# 4__Connectors___IO.net
KiCad netlist of a schematic drawn in Altium Designer
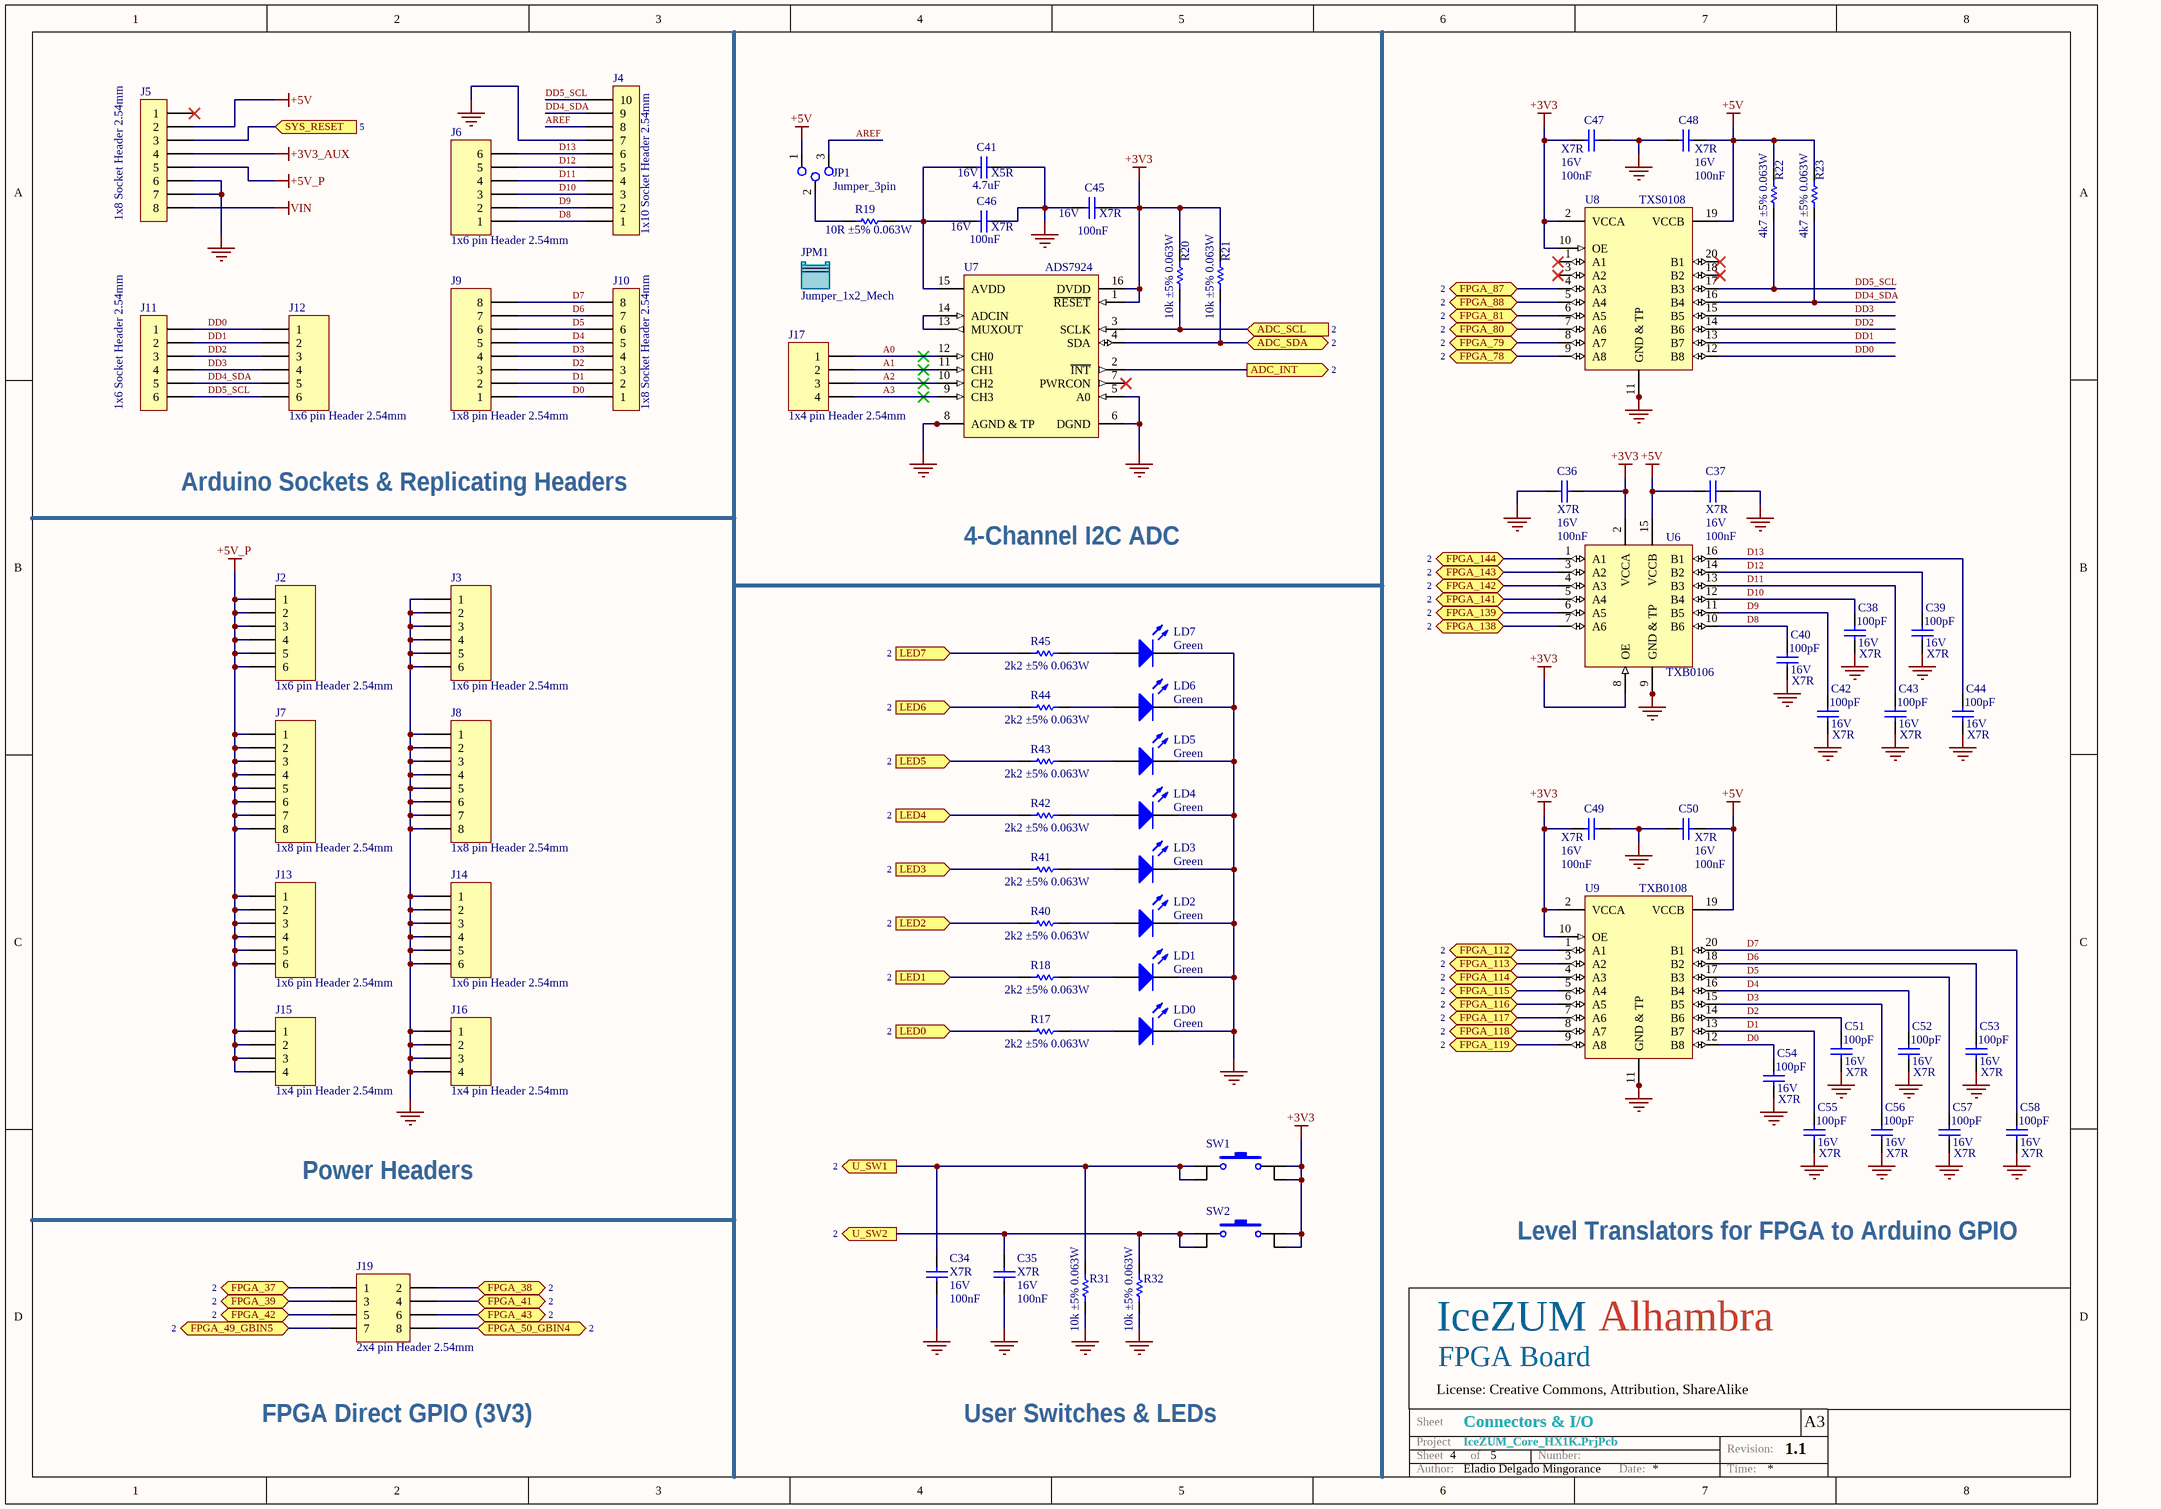
[diagram p0: [4]_Connectors_&_IO.SchDoc]

(export (version "E")
  (design (tool "Eeschema 10.0.6"))
  (components
    (comp (ref "C34")
      (value "Capacitor")
      (footprint "C0402")
      (description "Capacitor SMD")
      (fields
        (field (name "DIELECTRIC") "X7R")
        (field (name "VOLTAGE") "16V")
        (field (name "CAPACITANCE") "100nF")
        (field (name "PART NUMBER") "C0402_100nF_16V_±10%")
        (field (name "TOLERANCE") "±10%")
      )
      (libsource (lib "Pasives_Capacitor_SMD") (part "Capacitor"))
    )
    (comp (ref "C35")
      (value "Capacitor")
      (footprint "C0402")
      (description "Capacitor SMD")
      (fields
        (field (name "DIELECTRIC") "X7R")
        (field (name "VOLTAGE") "16V")
        (field (name "CAPACITANCE") "100nF")
        (field (name "PART NUMBER") "C0402_100nF_16V_±10%")
        (field (name "TOLERANCE") "±10%")
      )
      (libsource (lib "Pasives_Capacitor_SMD") (part "Capacitor"))
    )
    (comp (ref "C36")
      (value "Capacitor")
      (footprint "C0402")
      (description "Capacitor SMD")
      (fields
        (field (name "DIELECTRIC") "X7R")
        (field (name "VOLTAGE") "16V")
        (field (name "CAPACITANCE") "100nF")
        (field (name "PART NUMBER") "C0402_100nF_16V_±10%")
        (field (name "TOLERANCE") "±10%")
      )
      (libsource (lib "Pasives_Capacitor_SMD") (part "Capacitor"))
    )
    (comp (ref "C37")
      (value "Capacitor")
      (footprint "C0402")
      (description "Capacitor SMD")
      (fields
        (field (name "DIELECTRIC") "X7R")
        (field (name "VOLTAGE") "16V")
        (field (name "CAPACITANCE") "100nF")
        (field (name "PART NUMBER") "C0402_100nF_16V_±10%")
        (field (name "TOLERANCE") "±10%")
      )
      (libsource (lib "Pasives_Capacitor_SMD") (part "Capacitor"))
    )
    (comp (ref "C38")
      (value "Capacitor")
      (footprint "C0402")
      (description "Capacitor SMD")
      (fields
        (field (name "DIELECTRIC") "X7R")
        (field (name "VOLTAGE") "16V")
        (field (name "CAPACITANCE") "100pF")
        (field (name "PART NUMBER") "C0402_100pF_16V_±10%")
        (field (name "TOLERANCE") "±10%")
      )
      (libsource (lib "Pasives_Capacitor_SMD") (part "Capacitor"))
    )
    (comp (ref "C39")
      (value "Capacitor")
      (footprint "C0402")
      (description "Capacitor SMD")
      (fields
        (field (name "DIELECTRIC") "X7R")
        (field (name "VOLTAGE") "16V")
        (field (name "CAPACITANCE") "100pF")
        (field (name "PART NUMBER") "C0402_100pF_16V_±10%")
        (field (name "TOLERANCE") "±10%")
      )
      (libsource (lib "Pasives_Capacitor_SMD") (part "Capacitor"))
    )
    (comp (ref "C40")
      (value "Capacitor")
      (footprint "C0402")
      (description "Capacitor SMD")
      (fields
        (field (name "DIELECTRIC") "X7R")
        (field (name "VOLTAGE") "16V")
        (field (name "CAPACITANCE") "100pF")
        (field (name "PART NUMBER") "C0402_100pF_16V_±10%")
        (field (name "TOLERANCE") "±10%")
      )
      (libsource (lib "Pasives_Capacitor_SMD") (part "Capacitor"))
    )
    (comp (ref "C41")
      (value "Capacitor")
      (footprint "C0603")
      (description "Capacitor SMD")
      (fields
        (field (name "DIELECTRIC") "X5R")
        (field (name "VOLTAGE") "16V")
        (field (name "CAPACITANCE") "4.7uF")
        (field (name "PART NUMBER") "C0603_4.7uF_16V_±10%")
        (field (name "TOLERANCE") "±10%")
      )
      (libsource (lib "Pasives_Capacitor_SMD") (part "Capacitor"))
    )
    (comp (ref "C42")
      (value "Capacitor")
      (footprint "C0402")
      (description "Capacitor SMD")
      (fields
        (field (name "DIELECTRIC") "X7R")
        (field (name "VOLTAGE") "16V")
        (field (name "CAPACITANCE") "100pF")
        (field (name "PART NUMBER") "C0402_100pF_16V_±10%")
        (field (name "TOLERANCE") "±10%")
      )
      (libsource (lib "Pasives_Capacitor_SMD") (part "Capacitor"))
    )
    (comp (ref "C43")
      (value "Capacitor")
      (footprint "C0402")
      (description "Capacitor SMD")
      (fields
        (field (name "DIELECTRIC") "X7R")
        (field (name "VOLTAGE") "16V")
        (field (name "CAPACITANCE") "100pF")
        (field (name "PART NUMBER") "C0402_100pF_16V_±10%")
        (field (name "TOLERANCE") "±10%")
      )
      (libsource (lib "Pasives_Capacitor_SMD") (part "Capacitor"))
    )
    (comp (ref "C44")
      (value "Capacitor")
      (footprint "C0402")
      (description "Capacitor SMD")
      (fields
        (field (name "DIELECTRIC") "X7R")
        (field (name "VOLTAGE") "16V")
        (field (name "CAPACITANCE") "100pF")
        (field (name "PART NUMBER") "C0402_100pF_16V_±10%")
        (field (name "TOLERANCE") "±10%")
      )
      (libsource (lib "Pasives_Capacitor_SMD") (part "Capacitor"))
    )
    (comp (ref "C45")
      (value "Capacitor")
      (footprint "C0402")
      (description "Capacitor SMD")
      (fields
        (field (name "DIELECTRIC") "X7R")
        (field (name "VOLTAGE") "16V")
        (field (name "CAPACITANCE") "100nF")
        (field (name "PART NUMBER") "C0402_100nF_16V_±10%")
        (field (name "TOLERANCE") "±10%")
      )
      (libsource (lib "Pasives_Capacitor_SMD") (part "Capacitor"))
    )
    (comp (ref "C46")
      (value "Capacitor")
      (footprint "C0402")
      (description "Capacitor SMD")
      (fields
        (field (name "DIELECTRIC") "X7R")
        (field (name "VOLTAGE") "16V")
        (field (name "CAPACITANCE") "100nF")
        (field (name "PART NUMBER") "C0402_100nF_16V_±10%")
        (field (name "TOLERANCE") "±10%")
      )
      (libsource (lib "Pasives_Capacitor_SMD") (part "Capacitor"))
    )
    (comp (ref "C47")
      (value "Capacitor")
      (footprint "C0402")
      (description "Capacitor SMD")
      (fields
        (field (name "DIELECTRIC") "X7R")
        (field (name "VOLTAGE") "16V")
        (field (name "CAPACITANCE") "100nF")
        (field (name "PART NUMBER") "C0402_100nF_16V_±10%")
        (field (name "TOLERANCE") "±10%")
      )
      (libsource (lib "Pasives_Capacitor_SMD") (part "Capacitor"))
    )
    (comp (ref "C48")
      (value "Capacitor")
      (footprint "C0402")
      (description "Capacitor SMD")
      (fields
        (field (name "DIELECTRIC") "X7R")
        (field (name "VOLTAGE") "16V")
        (field (name "CAPACITANCE") "100nF")
        (field (name "PART NUMBER") "C0402_100nF_16V_±10%")
        (field (name "TOLERANCE") "±10%")
      )
      (libsource (lib "Pasives_Capacitor_SMD") (part "Capacitor"))
    )
    (comp (ref "C49")
      (value "Capacitor")
      (footprint "C0402")
      (description "Capacitor SMD")
      (fields
        (field (name "DIELECTRIC") "X7R")
        (field (name "VOLTAGE") "16V")
        (field (name "CAPACITANCE") "100nF")
        (field (name "PART NUMBER") "C0402_100nF_16V_±10%")
        (field (name "TOLERANCE") "±10%")
      )
      (libsource (lib "Pasives_Capacitor_SMD") (part "Capacitor"))
    )
    (comp (ref "C50")
      (value "Capacitor")
      (footprint "C0402")
      (description "Capacitor SMD")
      (fields
        (field (name "DIELECTRIC") "X7R")
        (field (name "VOLTAGE") "16V")
        (field (name "CAPACITANCE") "100nF")
        (field (name "PART NUMBER") "C0402_100nF_16V_±10%")
        (field (name "TOLERANCE") "±10%")
      )
      (libsource (lib "Pasives_Capacitor_SMD") (part "Capacitor"))
    )
    (comp (ref "C51")
      (value "Capacitor")
      (footprint "C0402")
      (description "Capacitor SMD")
      (fields
        (field (name "DIELECTRIC") "X7R")
        (field (name "VOLTAGE") "16V")
        (field (name "CAPACITANCE") "100pF")
        (field (name "PART NUMBER") "C0402_100pF_16V_±10%")
        (field (name "TOLERANCE") "±10%")
      )
      (libsource (lib "Pasives_Capacitor_SMD") (part "Capacitor"))
    )
    (comp (ref "C52")
      (value "Capacitor")
      (footprint "C0402")
      (description "Capacitor SMD")
      (fields
        (field (name "DIELECTRIC") "X7R")
        (field (name "VOLTAGE") "16V")
        (field (name "CAPACITANCE") "100pF")
        (field (name "PART NUMBER") "C0402_100pF_16V_±10%")
        (field (name "TOLERANCE") "±10%")
      )
      (libsource (lib "Pasives_Capacitor_SMD") (part "Capacitor"))
    )
    (comp (ref "C53")
      (value "Capacitor")
      (footprint "C0402")
      (description "Capacitor SMD")
      (fields
        (field (name "DIELECTRIC") "X7R")
        (field (name "VOLTAGE") "16V")
        (field (name "CAPACITANCE") "100pF")
        (field (name "PART NUMBER") "C0402_100pF_16V_±10%")
        (field (name "TOLERANCE") "±10%")
      )
      (libsource (lib "Pasives_Capacitor_SMD") (part "Capacitor"))
    )
    (comp (ref "C54")
      (value "Capacitor")
      (footprint "C0402")
      (description "Capacitor SMD")
      (fields
        (field (name "DIELECTRIC") "X7R")
        (field (name "VOLTAGE") "16V")
        (field (name "CAPACITANCE") "100pF")
        (field (name "PART NUMBER") "C0402_100pF_16V_±10%")
        (field (name "TOLERANCE") "±10%")
      )
      (libsource (lib "Pasives_Capacitor_SMD") (part "Capacitor"))
    )
    (comp (ref "C55")
      (value "Capacitor")
      (footprint "C0402")
      (description "Capacitor SMD")
      (fields
        (field (name "DIELECTRIC") "X7R")
        (field (name "VOLTAGE") "16V")
        (field (name "CAPACITANCE") "100pF")
        (field (name "PART NUMBER") "C0402_100pF_16V_±10%")
        (field (name "TOLERANCE") "±10%")
      )
      (libsource (lib "Pasives_Capacitor_SMD") (part "Capacitor"))
    )
    (comp (ref "C56")
      (value "Capacitor")
      (footprint "C0402")
      (description "Capacitor SMD")
      (fields
        (field (name "DIELECTRIC") "X7R")
        (field (name "VOLTAGE") "16V")
        (field (name "CAPACITANCE") "100pF")
        (field (name "PART NUMBER") "C0402_100pF_16V_±10%")
        (field (name "TOLERANCE") "±10%")
      )
      (libsource (lib "Pasives_Capacitor_SMD") (part "Capacitor"))
    )
    (comp (ref "C57")
      (value "Capacitor")
      (footprint "C0402")
      (description "Capacitor SMD")
      (fields
        (field (name "DIELECTRIC") "X7R")
        (field (name "VOLTAGE") "16V")
        (field (name "CAPACITANCE") "100pF")
        (field (name "PART NUMBER") "C0402_100pF_16V_±10%")
        (field (name "TOLERANCE") "±10%")
      )
      (libsource (lib "Pasives_Capacitor_SMD") (part "Capacitor"))
    )
    (comp (ref "C58")
      (value "Capacitor")
      (footprint "C0402")
      (description "Capacitor SMD")
      (fields
        (field (name "DIELECTRIC") "X7R")
        (field (name "VOLTAGE") "16V")
        (field (name "CAPACITANCE") "100pF")
        (field (name "PART NUMBER") "C0402_100pF_16V_±10%")
        (field (name "TOLERANCE") "±10%")
      )
      (libsource (lib "Pasives_Capacitor_SMD") (part "Capacitor"))
    )
    (comp (ref "J2")
      (value "1x6 pin Header 2.54mm")
      (footprint "1x6 Pin Header 2.54 Red")
      (fields (field (name "MANUFACTURER") "Samtec") (field (name "PART NUMBER") "CON_PH_THT2.54_6 Red"))
      (libsource (lib "Connector_PinHeader_2.54") (part "1x6 pin Header 2.54mm"))
    )
    (comp (ref "J3")
      (value "1x6 pin Header 2.54mm")
      (footprint "1x6 Pin Header 2.54")
      (fields (field (name "MANUFACTURER") "Samtec") (field (name "PART NUMBER") "CON_PH_THT2.54_6"))
      (libsource (lib "Connector_PinHeader_2.54") (part "1x6 pin Header 2.54mm"))
    )
    (comp (ref "J4")
      (value "1x10 Socket Header 2.54mm")
      (footprint "1x10 Socket Header THT 2.54mm")
      (description "Connector, 10 pin Socket Header 2.54mm")
      (fields (field (name "MANUFACTURER") "Samtec") (field (name "PART NUMBER") "CON_SH_THT2.54_10"))
      (libsource (lib "Connector_SocketHeader_2.54") (part "1x10 Socket Header 2.54mm"))
    )
    (comp (ref "J5")
      (value "1x8 Socket Header 2.54mm")
      (footprint "1x8 Socket Header THT 2.54mm")
      (description "8 pin Socket Header 2.54mm")
      (fields (field (name "MANUFACTURER") "Samtec") (field (name "PART NUMBER") "CON_SH_THT2.54_8"))
      (libsource (lib "") (part "1x8 Socket Header 2.54mm_1"))
    )
    (comp (ref "J6")
      (value "1x6 pin Header 2.54mm")
      (footprint "1x6 Pin Header 2.54 White")
      (fields (field (name "MANUFACTURER") "Samtec") (field (name "PART NUMBER") "CON_PH_THT2.54_6 Natural"))
      (libsource (lib "") (part "1x6 pin Header 2.54mm_1"))
    )
    (comp (ref "J7")
      (value "1x8 pin Header 2.54mm")
      (footprint "1x8 Pin Header 2.54 Red")
      (fields (field (name "MANUFACTURER") "Samtec") (field (name "PART NUMBER") "CON_PH_THT2.54_8 Red"))
      (libsource (lib "Connector_PinHeader_2.54") (part "1x8 pin Header 2.54mm"))
    )
    (comp (ref "J8")
      (value "1x8 pin Header 2.54mm")
      (footprint "1x8 Pin Header 2.54")
      (fields (field (name "MANUFACTURER") "Samtec") (field (name "PART NUMBER") "CON_PH_THT2.54_8"))
      (libsource (lib "Connector_PinHeader_2.54") (part "1x8 pin Header 2.54mm"))
    )
    (comp (ref "J9")
      (value "1x8 pin Header 2.54mm")
      (footprint "1x8 Pin Header 2.54 White")
      (fields (field (name "MANUFACTURER") "Samtec") (field (name "PART NUMBER") "CON_PH_THT2.54_8 Natural"))
      (libsource (lib "") (part "1x8 pin Header 2.54mm_1"))
    )
    (comp (ref "J10")
      (value "1x8 Socket Header 2.54mm")
      (footprint "1x8 Socket Header THT 2.54mm")
      (description "8 pin Socket Header 2.54mm")
      (fields (field (name "MANUFACTURER") "Samtec") (field (name "PART NUMBER") "CON_SH_THT2.54_8"))
      (libsource (lib "Connector_SocketHeader_2.54") (part "1x8 Socket Header 2.54mm"))
    )
    (comp (ref "J11")
      (value "1x6 Socket Header 2.54mm")
      (footprint "1x6 Socket Header THT 2.54mm")
      (description "6 pin Socket Header 2.54mm")
      (fields (field (name "MANUFACTURER") "Samtec") (field (name "PART NUMBER") "CON_SH_THT2.54_6"))
      (libsource (lib "Connector_SocketHeader_2.54") (part "1x6 Socket Header 2.54mm"))
    )
    (comp (ref "J12")
      (value "1x6 pin Header 2.54mm")
      (footprint "1x6 Pin Header 2.54 White")
      (description "Connector, 1x6 pin Header 2.54mm")
      (fields (field (name "MANUFACTURER") "Samtec") (field (name "PART NUMBER") "CON_PH_THT2.54_6 Natural"))
      (libsource (lib "Connector_PinHeader_2.54") (part "1x6 pin Header 2.54mm"))
    )
    (comp (ref "J13")
      (value "1x6 pin Header 2.54mm")
      (footprint "1x6 Pin Header 2.54 Red")
      (fields (field (name "MANUFACTURER") "Samtec") (field (name "PART NUMBER") "CON_PH_THT2.54_6 Red"))
      (libsource (lib "Connector_PinHeader_2.54") (part "1x6 pin Header 2.54mm"))
    )
    (comp (ref "J14")
      (value "1x6 pin Header 2.54mm")
      (footprint "1x6 Pin Header 2.54")
      (fields (field (name "MANUFACTURER") "Samtec") (field (name "PART NUMBER") "CON_PH_THT2.54_6"))
      (libsource (lib "Connector_PinHeader_2.54") (part "1x6 pin Header 2.54mm"))
    )
    (comp (ref "J15")
      (value "1x4 pin Header 2.54mm")
      (footprint "1x4 Pin Header 2.54 Red")
      (description "Connector, 1x4 pin Header 2.54mm")
      (fields (field (name "MANUFACTURER") "Samtec") (field (name "PART NUMBER") "CON_PH_THT2.54_4 Red"))
      (libsource (lib "Connector_PinHeader_2.54") (part "1x4 pin Header 2.54mm"))
    )
    (comp (ref "J16")
      (value "1x4 pin Header 2.54mm")
      (footprint "1x4 Pin Header 2.54")
      (description "Connector, 1x4 pin Header 2.54mm")
      (fields (field (name "MANUFACTURER") "Samtec") (field (name "PART NUMBER") "CON_PH_THT2.54_4"))
      (libsource (lib "Connector_PinHeader_2.54") (part "1x4 pin Header 2.54mm"))
    )
    (comp (ref "J17")
      (value "1x4 pin Header 2.54mm")
      (footprint "1x4 Pin Header 2.54 Blue")
      (description "Connector, 1x4 pin Header 2.54mm")
      (fields (field (name "MANUFACTURER") "Samtec") (field (name "PART NUMBER") "CON_PH_THT2.54_4 Blue"))
      (libsource (lib "") (part "1x4 pin Header 2.54mm_1"))
    )
    (comp (ref "J19")
      (value "2x4 pin Header 2.54mm")
      (footprint "2x4 Pin Header 2.54 Yellow")
      (description "Connector, 8 pin Dual Header 2.54mm")
      (fields (field (name "MANUFACTURER") "Samtec") (field (name "PART NUMBER") "CON_DPH_THT2.54_8"))
      (libsource (lib "Connector_PinHeader_2.54") (part "2x4 pin Header 2.54mm"))
    )
    (comp (ref "JP1")
      (value "Jumper_3pin")
      (footprint "1x3 Header 2.54 JP12")
      (description "Connector, Jumper, 3 pin Male Header 2.54mm")
      (fields (field (name "PART NUMBER") "Jumper_3pin_THT_JP12") (field (name "MANUFACTURER") "Würth"))
      (libsource (lib "Connector_Jumper") (part "Jumper_3pin"))
    )
    (comp (ref "JPM1")
      (value "Jumper_1x2_Mech")
      (description "Connector, Jumper, 1x2 Jumper 2.54mm")
      (fields (field (name "PART NUMBER") "Jumper_2pin_Mech") (field (name "MANUFACTURER") "Würth"))
      (libsource (lib "Connectors_Jumpers") (part "Jumper_1x2_Mech"))
    )
    (comp (ref "LD0")
      (value "Green")
      (footprint "LED0603")
      (description "LED")
      (fields (field (name "PART NUMBER") "LED Green 0603") (field (name "MANUFACTURER") "OSRAM Opto"))
      (libsource (lib "Optoelectronics") (part "LED"))
    )
    (comp (ref "LD1")
      (value "Green")
      (footprint "LED0603")
      (description "LED")
      (fields (field (name "PART NUMBER") "LED Green 0603") (field (name "MANUFACTURER") "OSRAM Opto"))
      (libsource (lib "Optoelectronics") (part "LED"))
    )
    (comp (ref "LD2")
      (value "Green")
      (footprint "LED0603")
      (description "LED")
      (fields (field (name "PART NUMBER") "LED Green 0603") (field (name "MANUFACTURER") "OSRAM Opto"))
      (libsource (lib "Optoelectronics") (part "LED"))
    )
    (comp (ref "LD3")
      (value "Green")
      (footprint "LED0603")
      (description "LED")
      (fields (field (name "PART NUMBER") "LED Green 0603") (field (name "MANUFACTURER") "OSRAM Opto"))
      (libsource (lib "Optoelectronics") (part "LED"))
    )
    (comp (ref "LD4")
      (value "Green")
      (footprint "LED0603")
      (description "LED")
      (fields (field (name "PART NUMBER") "LED Green 0603") (field (name "MANUFACTURER") "OSRAM Opto"))
      (libsource (lib "Optoelectronics") (part "LED"))
    )
    (comp (ref "LD5")
      (value "Green")
      (footprint "LED0603")
      (description "LED")
      (fields (field (name "PART NUMBER") "LED Green 0603") (field (name "MANUFACTURER") "OSRAM Opto"))
      (libsource (lib "Optoelectronics") (part "LED"))
    )
    (comp (ref "LD6")
      (value "Green")
      (footprint "LED0603")
      (description "LED")
      (fields (field (name "PART NUMBER") "LED Green 0603") (field (name "MANUFACTURER") "OSRAM Opto"))
      (libsource (lib "Optoelectronics") (part "LED"))
    )
    (comp (ref "LD7")
      (value "Green")
      (footprint "LED0603")
      (description "LED")
      (fields (field (name "PART NUMBER") "LED Green 0603") (field (name "MANUFACTURER") "OSRAM Opto"))
      (libsource (lib "Optoelectronics") (part "LED"))
    )
    (comp (ref "R17")
      (value "2k2 ±5% 0.063W")
      (footprint "R0402")
      (description "Resistor, SMD")
      (fields (field (name "TOLERANCE") "±5%") (field (name "POWER") "0.063W"))
      (libsource (lib "Pasives_Resistor_SMD") (part "Resistor"))
    )
    (comp (ref "R18")
      (value "2k2 ±5% 0.063W")
      (footprint "R0402")
      (description "Resistor, SMD")
      (fields (field (name "TOLERANCE") "±5%") (field (name "POWER") "0.063W"))
      (libsource (lib "Pasives_Resistor_SMD") (part "Resistor"))
    )
    (comp (ref "R19")
      (value "10R ±5% 0.063W")
      (footprint "R0402")
      (description "Resistor, SMD")
      (fields (field (name "TOLERANCE") "±5%") (field (name "POWER") "0.063W"))
      (libsource (lib "Pasives_Resistor_SMD") (part "Resistor"))
    )
    (comp (ref "R20")
      (value "10k ±5% 0.063W")
      (footprint "R0402")
      (description "Resistor, SMD")
      (fields (field (name "TOLERANCE") "±5%") (field (name "POWER") "0.063W"))
      (libsource (lib "Pasives_Resistor_SMD") (part "Resistor"))
    )
    (comp (ref "R21")
      (value "10k ±5% 0.063W")
      (footprint "R0402")
      (description "Resistor, SMD")
      (fields (field (name "TOLERANCE") "±5%") (field (name "POWER") "0.063W"))
      (libsource (lib "Pasives_Resistor_SMD") (part "Resistor"))
    )
    (comp (ref "R22")
      (value "4k7 ±5% 0.063W")
      (footprint "R0402")
      (description "Resistor, SMD")
      (fields (field (name "TOLERANCE") "±5%") (field (name "POWER") "0.063W"))
      (libsource (lib "Pasives_Resistor_SMD") (part "Resistor"))
    )
    (comp (ref "R23")
      (value "4k7 ±5% 0.063W")
      (footprint "R0402")
      (description "Resistor, SMD")
      (fields (field (name "TOLERANCE") "±5%") (field (name "POWER") "0.063W"))
      (libsource (lib "Pasives_Resistor_SMD") (part "Resistor"))
    )
    (comp (ref "R31")
      (value "10k ±5% 0.063W")
      (footprint "R0402")
      (description "Resistor, SMD")
      (fields (field (name "TOLERANCE") "±5%") (field (name "POWER") "0.063W"))
      (libsource (lib "Pasives_Resistor_SMD") (part "Resistor"))
    )
    (comp (ref "R32")
      (value "10k ±5% 0.063W")
      (footprint "R0402")
      (description "Resistor, SMD")
      (fields (field (name "TOLERANCE") "±5%") (field (name "POWER") "0.063W"))
      (libsource (lib "Pasives_Resistor_SMD") (part "Resistor"))
    )
    (comp (ref "R40")
      (value "2k2 ±5% 0.063W")
      (footprint "R0402")
      (description "Resistor, SMD")
      (fields (field (name "TOLERANCE") "±5%") (field (name "POWER") "0.063W"))
      (libsource (lib "Pasives_Resistor_SMD") (part "Resistor"))
    )
    (comp (ref "R41")
      (value "2k2 ±5% 0.063W")
      (footprint "R0402")
      (description "Resistor, SMD")
      (fields (field (name "TOLERANCE") "±5%") (field (name "POWER") "0.063W"))
      (libsource (lib "Pasives_Resistor_SMD") (part "Resistor"))
    )
    (comp (ref "R42")
      (value "2k2 ±5% 0.063W")
      (footprint "R0402")
      (description "Resistor, SMD")
      (fields (field (name "TOLERANCE") "±5%") (field (name "POWER") "0.063W"))
      (libsource (lib "Pasives_Resistor_SMD") (part "Resistor"))
    )
    (comp (ref "R43")
      (value "2k2 ±5% 0.063W")
      (footprint "R0402")
      (description "Resistor, SMD")
      (fields (field (name "TOLERANCE") "±5%") (field (name "POWER") "0.063W"))
      (libsource (lib "Pasives_Resistor_SMD") (part "Resistor"))
    )
    (comp (ref "R44")
      (value "2k2 ±5% 0.063W")
      (footprint "R0402")
      (description "Resistor, SMD")
      (fields (field (name "TOLERANCE") "±5%") (field (name "POWER") "0.063W"))
      (libsource (lib "Pasives_Resistor_SMD") (part "Resistor"))
    )
    (comp (ref "R45")
      (value "2k2 ±5% 0.063W")
      (footprint "R0402")
      (description "Resistor, SMD")
      (fields (field (name "TOLERANCE") "±5%") (field (name "POWER") "0.063W"))
      (libsource (lib "Pasives_Resistor_SMD") (part "Resistor"))
    )
    (comp (ref "SW1")
      (value "Switch_4P_SP")
      (footprint "WE_434331013822")
      (description "Micro miniature pushbutton surface Switch")
      (fields
        (field (name "PART NUMBER") "SW 3.5x2.9 mm SMD side push")
        (field (name "MANUFACTURER") "Würth")
      )
      (libsource (lib "Electromechanical") (part "Switch_4P_SP"))
    )
    (comp (ref "SW2")
      (value "Switch_4P_SP")
      (footprint "WE_434331013822")
      (description "Micro miniature pushbutton surface Switch")
      (fields
        (field (name "PART NUMBER") "SW 3.5x2.9 mm SMD side push")
        (field (name "MANUFACTURER") "Würth")
      )
      (libsource (lib "Electromechanical") (part "Switch_4P_SP"))
    )
    (comp (ref "U6")
      (value "TXB0106")
      (footprint "QFN16")
      (description "Voltage Translator, Hex")
      (fields (field (name "MANUFACTURER") "Texas Instruments"))
      (libsource (lib "Voltage_translator") (part "TXB0106"))
    )
    (comp (ref "U7")
      (value "ADS7924")
      (footprint "QFN16")
      (description "ADC Converter, 12-Bit, 4-Ch, I2C")
      (fields (field (name "MANUFACTURER") "Texas Instruments"))
      (libsource (lib "Data_Converters") (part "ADS7924"))
    )
    (comp (ref "U8")
      (value "TXS0108")
      (footprint "VQFN20 4.5x3.5mm")
      (description "Voltage Level Translator, 8-Bit Bidir., with TP")
      (fields (field (name "MANUFACTURER") "Texas Instruments"))
      (libsource (lib "Voltage_translator") (part "TXB0108RGY"))
    )
    (comp (ref "U9")
      (value "TXB0108")
      (footprint "VQFN20 4.5x3.5mm")
      (description "Voltage Level Translator, 8-Bit Bidir., with TP")
      (fields (field (name "MANUFACTURER") "Texas Instruments"))
      (libsource (lib "Voltage_translator") (part "TXB0108RGY"))
    )
  )
  (nets
    (net (code "1") (name "+3V3") (class "Default")
      (node (ref "C36") (pin "1") (pinfunction "1_1") (pintype "passive"))
      (node (ref "C45") (pin "2") (pinfunction "2_2") (pintype "passive"))
      (node (ref "C47") (pin "2") (pinfunction "2_2") (pintype "passive"))
      (node (ref "C49") (pin "2") (pinfunction "2_2") (pintype "passive"))
      (node (ref "R20") (pin "2") (pinfunction "2_2") (pintype "passive"))
      (node (ref "R21") (pin "2") (pinfunction "2_2") (pintype "passive"))
      (node (ref "SW1") (pin "3") (pinfunction "3_3") (pintype "passive"))
      (node (ref "SW1") (pin "4") (pinfunction "4_4") (pintype "passive"))
      (node (ref "SW2") (pin "3") (pinfunction "3_3") (pintype "passive"))
      (node (ref "SW2") (pin "4") (pinfunction "4_4") (pintype "passive"))
      (node (ref "U6") (pin "2") (pinfunction "VCCA_2") (pintype "power_in"))
      (node (ref "U6") (pin "8") (pinfunction "OE_8") (pintype "input"))
      (node (ref "U7") (pin "1") (pinfunction "RESET_1") (pintype "input"))
      (node (ref "U7") (pin "16") (pinfunction "DVDD_16") (pintype "power_in"))
      (node (ref "U8") (pin "10") (pinfunction "OE_10") (pintype "input"))
      (node (ref "U8") (pin "2") (pinfunction "VCCA_2") (pintype "power_in"))
      (node (ref "U9") (pin "10") (pinfunction "OE_10") (pintype "input"))
      (node (ref "U9") (pin "2") (pinfunction "VCCA_2") (pintype "power_in"))
    )
    (net (code "2") (name "+3V3_AUX") (class "Default")
      (node (ref "J5") (pin "4") (pinfunction "4_4") (pintype "passive"))
    )
    (net (code "3") (name "+5V") (class "Default")
      (node (ref "C37") (pin "2") (pinfunction "2_2") (pintype "passive"))
      (node (ref "C48") (pin "1") (pinfunction "1_1") (pintype "passive"))
      (node (ref "C50") (pin "1") (pinfunction "1_1") (pintype "passive"))
      (node (ref "J5") (pin "2") (pinfunction "2_2") (pintype "passive"))
      (node (ref "JP1") (pin "1") (pinfunction "1_1") (pintype "passive"))
      (node (ref "R22") (pin "2") (pinfunction "2_2") (pintype "passive"))
      (node (ref "R23") (pin "2") (pinfunction "2_2") (pintype "passive"))
      (node (ref "U6") (pin "15") (pinfunction "VCCB_15") (pintype "power_in"))
      (node (ref "U8") (pin "19") (pinfunction "VCCB_19") (pintype "power_in"))
      (node (ref "U9") (pin "19") (pinfunction "VCCB_19") (pintype "power_in"))
    )
    (net (code "4") (name "+5V_P") (class "Default")
      (node (ref "J13") (pin "1") (pinfunction "1_1") (pintype "passive"))
      (node (ref "J13") (pin "2") (pinfunction "2_2") (pintype "passive"))
      (node (ref "J13") (pin "3") (pinfunction "3_3") (pintype "passive"))
      (node (ref "J13") (pin "4") (pinfunction "4_4") (pintype "passive"))
      (node (ref "J13") (pin "5") (pinfunction "5_5") (pintype "passive"))
      (node (ref "J13") (pin "6") (pinfunction "6_6") (pintype "passive"))
      (node (ref "J15") (pin "1") (pinfunction "1_1") (pintype "passive"))
      (node (ref "J15") (pin "2") (pinfunction "2_2") (pintype "passive"))
      (node (ref "J15") (pin "3") (pinfunction "3_3") (pintype "passive"))
      (node (ref "J15") (pin "4") (pinfunction "4_4") (pintype "passive"))
      (node (ref "J2") (pin "1") (pinfunction "1_1") (pintype "passive"))
      (node (ref "J2") (pin "2") (pinfunction "2_2") (pintype "passive"))
      (node (ref "J2") (pin "3") (pinfunction "3_3") (pintype "passive"))
      (node (ref "J2") (pin "4") (pinfunction "4_4") (pintype "passive"))
      (node (ref "J2") (pin "5") (pinfunction "5_5") (pintype "passive"))
      (node (ref "J2") (pin "6") (pinfunction "6_6") (pintype "passive"))
      (node (ref "J5") (pin "5") (pinfunction "5_5") (pintype "passive"))
      (node (ref "J7") (pin "1") (pinfunction "1_1") (pintype "passive"))
      (node (ref "J7") (pin "2") (pinfunction "2_2") (pintype "passive"))
      (node (ref "J7") (pin "3") (pinfunction "3_3") (pintype "passive"))
      (node (ref "J7") (pin "4") (pinfunction "4_4") (pintype "passive"))
      (node (ref "J7") (pin "5") (pinfunction "5_5") (pintype "passive"))
      (node (ref "J7") (pin "6") (pinfunction "6_6") (pintype "passive"))
      (node (ref "J7") (pin "7") (pinfunction "7_7") (pintype "passive"))
      (node (ref "J7") (pin "8") (pinfunction "8_8") (pintype "passive"))
    )
    (net (code "5") (name "/A0") (class "Default")
      (node (ref "J17") (pin "1") (pinfunction "1_1") (pintype "passive"))
      (node (ref "U7") (pin "12") (pinfunction "CH0_12") (pintype "input"))
    )
    (net (code "6") (name "/A1") (class "Default")
      (node (ref "J17") (pin "2") (pinfunction "2_2") (pintype "passive"))
      (node (ref "U7") (pin "11") (pinfunction "CH1_11") (pintype "input"))
    )
    (net (code "7") (name "/A2") (class "Default")
      (node (ref "J17") (pin "3") (pinfunction "3_3") (pintype "passive"))
      (node (ref "U7") (pin "10") (pinfunction "CH2_10") (pintype "input"))
    )
    (net (code "8") (name "/A3") (class "Default")
      (node (ref "J17") (pin "4") (pinfunction "4_4") (pintype "passive"))
      (node (ref "U7") (pin "9") (pinfunction "CH3_9") (pintype "input"))
    )
    (net (code "9") (name "/ADC_INT") (class "Default")
      (node (ref "U7") (pin "2") (pinfunction "INT_2") (pintype "output"))
    )
    (net (code "10") (name "/ADC_SCL") (class "Default")
      (node (ref "R20") (pin "1") (pinfunction "1_1") (pintype "passive"))
      (node (ref "U7") (pin "3") (pinfunction "SCLK_3") (pintype "input"))
    )
    (net (code "11") (name "/ADC_SDA") (class "Default")
      (node (ref "R21") (pin "1") (pinfunction "1_1") (pintype "passive"))
      (node (ref "U7") (pin "4") (pinfunction "SDA_4") (pintype "bidirectional"))
    )
    (net (code "12") (name "/AREF") (class "Default")
      (node (ref "J4") (pin "8") (pinfunction "8_8") (pintype "passive"))
      (node (ref "JP1") (pin "3") (pinfunction "3_3") (pintype "passive"))
    )
    (net (code "13") (name "/D0") (class "Default")
      (node (ref "C54") (pin "2") (pinfunction "2_2") (pintype "passive"))
      (node (ref "J10") (pin "1") (pinfunction "1_1") (pintype "passive"))
      (node (ref "J9") (pin "1") (pinfunction "1_1") (pintype "passive"))
      (node (ref "U9") (pin "12") (pinfunction "B8_12") (pintype "bidirectional"))
    )
    (net (code "14") (name "/D1") (class "Default")
      (node (ref "C55") (pin "2") (pinfunction "2_2") (pintype "passive"))
      (node (ref "J10") (pin "2") (pinfunction "2_2") (pintype "passive"))
      (node (ref "J9") (pin "2") (pinfunction "2_2") (pintype "passive"))
      (node (ref "U9") (pin "13") (pinfunction "B7_13") (pintype "bidirectional"))
    )
    (net (code "15") (name "/D2") (class "Default")
      (node (ref "C51") (pin "2") (pinfunction "2_2") (pintype "passive"))
      (node (ref "J10") (pin "3") (pinfunction "3_3") (pintype "passive"))
      (node (ref "J9") (pin "3") (pinfunction "3_3") (pintype "passive"))
      (node (ref "U9") (pin "14") (pinfunction "B6_14") (pintype "bidirectional"))
    )
    (net (code "16") (name "/D3") (class "Default")
      (node (ref "C56") (pin "2") (pinfunction "2_2") (pintype "passive"))
      (node (ref "J10") (pin "4") (pinfunction "4_4") (pintype "passive"))
      (node (ref "J9") (pin "4") (pinfunction "4_4") (pintype "passive"))
      (node (ref "U9") (pin "15") (pinfunction "B5_15") (pintype "bidirectional"))
    )
    (net (code "17") (name "/D4") (class "Default")
      (node (ref "C52") (pin "2") (pinfunction "2_2") (pintype "passive"))
      (node (ref "J10") (pin "5") (pinfunction "5_5") (pintype "passive"))
      (node (ref "J9") (pin "5") (pinfunction "5_5") (pintype "passive"))
      (node (ref "U9") (pin "16") (pinfunction "B4_16") (pintype "bidirectional"))
    )
    (net (code "18") (name "/D5") (class "Default")
      (node (ref "C57") (pin "2") (pinfunction "2_2") (pintype "passive"))
      (node (ref "J10") (pin "6") (pinfunction "6_6") (pintype "passive"))
      (node (ref "J9") (pin "6") (pinfunction "6_6") (pintype "passive"))
      (node (ref "U9") (pin "17") (pinfunction "B3_17") (pintype "bidirectional"))
    )
    (net (code "19") (name "/D6") (class "Default")
      (node (ref "C53") (pin "2") (pinfunction "2_2") (pintype "passive"))
      (node (ref "J10") (pin "7") (pinfunction "7_7") (pintype "passive"))
      (node (ref "J9") (pin "7") (pinfunction "7_7") (pintype "passive"))
      (node (ref "U9") (pin "18") (pinfunction "B2_18") (pintype "bidirectional"))
    )
    (net (code "20") (name "/D7") (class "Default")
      (node (ref "C58") (pin "2") (pinfunction "2_2") (pintype "passive"))
      (node (ref "J10") (pin "8") (pinfunction "8_8") (pintype "passive"))
      (node (ref "J9") (pin "8") (pinfunction "8_8") (pintype "passive"))
      (node (ref "U9") (pin "20") (pinfunction "B1_20") (pintype "bidirectional"))
    )
    (net (code "21") (name "/D8") (class "Default")
      (node (ref "C40") (pin "2") (pinfunction "2_2") (pintype "passive"))
      (node (ref "J4") (pin "1") (pinfunction "1_1") (pintype "passive"))
      (node (ref "J6") (pin "1") (pinfunction "1_1") (pintype "passive"))
      (node (ref "U6") (pin "10") (pinfunction "B6_10") (pintype "bidirectional"))
    )
    (net (code "22") (name "/D9") (class "Default")
      (node (ref "C42") (pin "2") (pinfunction "2_2") (pintype "passive"))
      (node (ref "J4") (pin "2") (pinfunction "2_2") (pintype "passive"))
      (node (ref "J6") (pin "2") (pinfunction "2_2") (pintype "passive"))
      (node (ref "U6") (pin "11") (pinfunction "B5_11") (pintype "bidirectional"))
    )
    (net (code "23") (name "/D10") (class "Default")
      (node (ref "C38") (pin "2") (pinfunction "2_2") (pintype "passive"))
      (node (ref "J4") (pin "3") (pinfunction "3_3") (pintype "passive"))
      (node (ref "J6") (pin "3") (pinfunction "3_3") (pintype "passive"))
      (node (ref "U6") (pin "12") (pinfunction "B4_12") (pintype "bidirectional"))
    )
    (net (code "24") (name "/D11") (class "Default")
      (node (ref "C43") (pin "2") (pinfunction "2_2") (pintype "passive"))
      (node (ref "J4") (pin "4") (pinfunction "4_4") (pintype "passive"))
      (node (ref "J6") (pin "4") (pinfunction "4_4") (pintype "passive"))
      (node (ref "U6") (pin "13") (pinfunction "B3_13") (pintype "bidirectional"))
    )
    (net (code "25") (name "/D12") (class "Default")
      (node (ref "C39") (pin "2") (pinfunction "2_2") (pintype "passive"))
      (node (ref "J4") (pin "5") (pinfunction "5_5") (pintype "passive"))
      (node (ref "J6") (pin "5") (pinfunction "5_5") (pintype "passive"))
      (node (ref "U6") (pin "14") (pinfunction "B2_14") (pintype "bidirectional"))
    )
    (net (code "26") (name "/D13") (class "Default")
      (node (ref "C44") (pin "2") (pinfunction "2_2") (pintype "passive"))
      (node (ref "J4") (pin "6") (pinfunction "6_6") (pintype "passive"))
      (node (ref "J6") (pin "6") (pinfunction "6_6") (pintype "passive"))
      (node (ref "U6") (pin "16") (pinfunction "B1_16") (pintype "bidirectional"))
    )
    (net (code "27") (name "/DD0") (class "Default")
      (node (ref "J11") (pin "1") (pinfunction "1_1") (pintype "passive"))
      (node (ref "J12") (pin "1") (pinfunction "1_1") (pintype "passive"))
      (node (ref "U8") (pin "12") (pinfunction "B8_12") (pintype "bidirectional"))
    )
    (net (code "28") (name "/DD1") (class "Default")
      (node (ref "J11") (pin "2") (pinfunction "2_2") (pintype "passive"))
      (node (ref "J12") (pin "2") (pinfunction "2_2") (pintype "passive"))
      (node (ref "U8") (pin "13") (pinfunction "B7_13") (pintype "bidirectional"))
    )
    (net (code "29") (name "/DD2") (class "Default")
      (node (ref "J11") (pin "3") (pinfunction "3_3") (pintype "passive"))
      (node (ref "J12") (pin "3") (pinfunction "3_3") (pintype "passive"))
      (node (ref "U8") (pin "14") (pinfunction "B6_14") (pintype "bidirectional"))
    )
    (net (code "30") (name "/DD3") (class "Default")
      (node (ref "J11") (pin "4") (pinfunction "4_4") (pintype "passive"))
      (node (ref "J12") (pin "4") (pinfunction "4_4") (pintype "passive"))
      (node (ref "U8") (pin "15") (pinfunction "B5_15") (pintype "bidirectional"))
    )
    (net (code "31") (name "/DD4_SDA") (class "Default")
      (node (ref "J11") (pin "5") (pinfunction "5_5") (pintype "passive"))
      (node (ref "J12") (pin "5") (pinfunction "5_5") (pintype "passive"))
      (node (ref "J4") (pin "9") (pinfunction "9_9") (pintype "passive"))
      (node (ref "R23") (pin "1") (pinfunction "1_1") (pintype "passive"))
      (node (ref "U8") (pin "16") (pinfunction "B4_16") (pintype "bidirectional"))
    )
    (net (code "32") (name "/DD5_SCL") (class "Default")
      (node (ref "J11") (pin "6") (pinfunction "6_6") (pintype "passive"))
      (node (ref "J12") (pin "6") (pinfunction "6_6") (pintype "passive"))
      (node (ref "J4") (pin "10") (pinfunction "10_10") (pintype "passive"))
      (node (ref "R22") (pin "1") (pinfunction "1_1") (pintype "passive"))
      (node (ref "U8") (pin "17") (pinfunction "B3_17") (pintype "bidirectional"))
    )
    (net (code "33") (name "/FPGA_37") (class "Default")
      (node (ref "J19") (pin "1") (pinfunction "1_1") (pintype "passive"))
    )
    (net (code "34") (name "/FPGA_38") (class "Default")
      (node (ref "J19") (pin "2") (pinfunction "2_2") (pintype "passive"))
    )
    (net (code "35") (name "/FPGA_39") (class "Default")
      (node (ref "J19") (pin "3") (pinfunction "3_3") (pintype "passive"))
    )
    (net (code "36") (name "/FPGA_41") (class "Default")
      (node (ref "J19") (pin "4") (pinfunction "4_4") (pintype "passive"))
    )
    (net (code "37") (name "/FPGA_42") (class "Default")
      (node (ref "J19") (pin "5") (pinfunction "5_5") (pintype "passive"))
    )
    (net (code "38") (name "/FPGA_43") (class "Default")
      (node (ref "J19") (pin "6") (pinfunction "6_6") (pintype "passive"))
    )
    (net (code "39") (name "/FPGA_49_GBIN5") (class "Default")
      (node (ref "J19") (pin "7") (pinfunction "7_7") (pintype "passive"))
    )
    (net (code "40") (name "/FPGA_50_GBIN4") (class "Default")
      (node (ref "J19") (pin "8") (pinfunction "8_8") (pintype "passive"))
    )
    (net (code "41") (name "/FPGA_78") (class "Default")
      (node (ref "U8") (pin "9") (pinfunction "A8_9") (pintype "bidirectional"))
    )
    (net (code "42") (name "/FPGA_79") (class "Default")
      (node (ref "U8") (pin "8") (pinfunction "A7_8") (pintype "bidirectional"))
    )
    (net (code "43") (name "/FPGA_80") (class "Default")
      (node (ref "U8") (pin "7") (pinfunction "A6_7") (pintype "bidirectional"))
    )
    (net (code "44") (name "/FPGA_81") (class "Default")
      (node (ref "U8") (pin "6") (pinfunction "A5_6") (pintype "bidirectional"))
    )
    (net (code "45") (name "/FPGA_87") (class "Default")
      (node (ref "U8") (pin "4") (pinfunction "A3_4") (pintype "bidirectional"))
    )
    (net (code "46") (name "/FPGA_88") (class "Default")
      (node (ref "U8") (pin "5") (pinfunction "A4_5") (pintype "bidirectional"))
    )
    (net (code "47") (name "/FPGA_112") (class "Default")
      (node (ref "U9") (pin "1") (pinfunction "A1_1") (pintype "bidirectional"))
    )
    (net (code "48") (name "/FPGA_113") (class "Default")
      (node (ref "U9") (pin "3") (pinfunction "A2_3") (pintype "bidirectional"))
    )
    (net (code "49") (name "/FPGA_114") (class "Default")
      (node (ref "U9") (pin "4") (pinfunction "A3_4") (pintype "bidirectional"))
    )
    (net (code "50") (name "/FPGA_115") (class "Default")
      (node (ref "U9") (pin "5") (pinfunction "A4_5") (pintype "bidirectional"))
    )
    (net (code "51") (name "/FPGA_116") (class "Default")
      (node (ref "U9") (pin "6") (pinfunction "A5_6") (pintype "bidirectional"))
    )
    (net (code "52") (name "/FPGA_117") (class "Default")
      (node (ref "U9") (pin "7") (pinfunction "A6_7") (pintype "bidirectional"))
    )
    (net (code "53") (name "/FPGA_118") (class "Default")
      (node (ref "U9") (pin "8") (pinfunction "A7_8") (pintype "bidirectional"))
    )
    (net (code "54") (name "/FPGA_119") (class "Default")
      (node (ref "U9") (pin "9") (pinfunction "A8_9") (pintype "bidirectional"))
    )
    (net (code "55") (name "/FPGA_138") (class "Default")
      (node (ref "U6") (pin "7") (pinfunction "A6_7") (pintype "bidirectional"))
    )
    (net (code "56") (name "/FPGA_139") (class "Default")
      (node (ref "U6") (pin "6") (pinfunction "A5_6") (pintype "bidirectional"))
    )
    (net (code "57") (name "/FPGA_141") (class "Default")
      (node (ref "U6") (pin "5") (pinfunction "A4_5") (pintype "bidirectional"))
    )
    (net (code "58") (name "/FPGA_142") (class "Default")
      (node (ref "U6") (pin "4") (pinfunction "A3_4") (pintype "bidirectional"))
    )
    (net (code "59") (name "/FPGA_143") (class "Default")
      (node (ref "U6") (pin "3") (pinfunction "A2_3") (pintype "bidirectional"))
    )
    (net (code "60") (name "/FPGA_144") (class "Default")
      (node (ref "U6") (pin "1") (pinfunction "A1_1") (pintype "bidirectional"))
    )
    (net (code "61") (name "/LED0") (class "Default")
      (node (ref "R17") (pin "1") (pinfunction "1_1") (pintype "passive"))
    )
    (net (code "62") (name "/LED1") (class "Default")
      (node (ref "R18") (pin "1") (pinfunction "1_1") (pintype "passive"))
    )
    (net (code "63") (name "/LED2") (class "Default")
      (node (ref "R40") (pin "1") (pinfunction "1_1") (pintype "passive"))
    )
    (net (code "64") (name "/LED3") (class "Default")
      (node (ref "R41") (pin "1") (pinfunction "1_1") (pintype "passive"))
    )
    (net (code "65") (name "/LED4") (class "Default")
      (node (ref "R42") (pin "1") (pinfunction "1_1") (pintype "passive"))
    )
    (net (code "66") (name "/LED5") (class "Default")
      (node (ref "R43") (pin "1") (pinfunction "1_1") (pintype "passive"))
    )
    (net (code "67") (name "/LED6") (class "Default")
      (node (ref "R44") (pin "1") (pinfunction "1_1") (pintype "passive"))
    )
    (net (code "68") (name "/LED7") (class "Default")
      (node (ref "R45") (pin "1") (pinfunction "1_1") (pintype "passive"))
    )
    (net (code "69") (name "/SYS_RESET") (class "Default")
      (node (ref "J5") (pin "3") (pinfunction "3_3") (pintype "passive"))
    )
    (net (code "70") (name "/U_SW1") (class "Default")
      (node (ref "C34") (pin "2") (pinfunction "2_2") (pintype "passive"))
      (node (ref "R31") (pin "2") (pinfunction "2_2") (pintype "passive"))
      (node (ref "SW1") (pin "1") (pinfunction "1_1") (pintype "passive"))
      (node (ref "SW1") (pin "2") (pinfunction "2_2") (pintype "passive"))
    )
    (net (code "71") (name "/U_SW2") (class "Default")
      (node (ref "C35") (pin "2") (pinfunction "2_2") (pintype "passive"))
      (node (ref "R32") (pin "2") (pinfunction "2_2") (pintype "passive"))
      (node (ref "SW2") (pin "1") (pinfunction "1_1") (pintype "passive"))
      (node (ref "SW2") (pin "2") (pinfunction "2_2") (pintype "passive"))
    )
    (net (code "72") (name "GND") (class "Default")
      (node (ref "C34") (pin "1") (pinfunction "1_1") (pintype "passive"))
      (node (ref "C35") (pin "1") (pinfunction "1_1") (pintype "passive"))
      (node (ref "C36") (pin "2") (pinfunction "2_2") (pintype "passive"))
      (node (ref "C37") (pin "1") (pinfunction "1_1") (pintype "passive"))
      (node (ref "C38") (pin "1") (pinfunction "1_1") (pintype "passive"))
      (node (ref "C39") (pin "1") (pinfunction "1_1") (pintype "passive"))
      (node (ref "C40") (pin "1") (pinfunction "1_1") (pintype "passive"))
      (node (ref "C41") (pin "1") (pinfunction "1_1") (pintype "passive"))
      (node (ref "C42") (pin "1") (pinfunction "1_1") (pintype "passive"))
      (node (ref "C43") (pin "1") (pinfunction "1_1") (pintype "passive"))
      (node (ref "C44") (pin "1") (pinfunction "1_1") (pintype "passive"))
      (node (ref "C45") (pin "1") (pinfunction "1_1") (pintype "passive"))
      (node (ref "C46") (pin "2") (pinfunction "2_2") (pintype "passive"))
      (node (ref "C47") (pin "1") (pinfunction "1_1") (pintype "passive"))
      (node (ref "C48") (pin "2") (pinfunction "2_2") (pintype "passive"))
      (node (ref "C49") (pin "1") (pinfunction "1_1") (pintype "passive"))
      (node (ref "C50") (pin "2") (pinfunction "2_2") (pintype "passive"))
      (node (ref "C51") (pin "1") (pinfunction "1_1") (pintype "passive"))
      (node (ref "C52") (pin "1") (pinfunction "1_1") (pintype "passive"))
      (node (ref "C53") (pin "1") (pinfunction "1_1") (pintype "passive"))
      (node (ref "C54") (pin "1") (pinfunction "1_1") (pintype "passive"))
      (node (ref "C55") (pin "1") (pinfunction "1_1") (pintype "passive"))
      (node (ref "C56") (pin "1") (pinfunction "1_1") (pintype "passive"))
      (node (ref "C57") (pin "1") (pinfunction "1_1") (pintype "passive"))
      (node (ref "C58") (pin "1") (pinfunction "1_1") (pintype "passive"))
      (node (ref "J14") (pin "1") (pinfunction "1_1") (pintype "passive"))
      (node (ref "J14") (pin "2") (pinfunction "2_2") (pintype "passive"))
      (node (ref "J14") (pin "3") (pinfunction "3_3") (pintype "passive"))
      (node (ref "J14") (pin "4") (pinfunction "4_4") (pintype "passive"))
      (node (ref "J14") (pin "5") (pinfunction "5_5") (pintype "passive"))
      (node (ref "J14") (pin "6") (pinfunction "6_6") (pintype "passive"))
      (node (ref "J16") (pin "1") (pinfunction "1_1") (pintype "passive"))
      (node (ref "J16") (pin "2") (pinfunction "2_2") (pintype "passive"))
      (node (ref "J16") (pin "3") (pinfunction "3_3") (pintype "passive"))
      (node (ref "J16") (pin "4") (pinfunction "4_4") (pintype "passive"))
      (node (ref "J3") (pin "1") (pinfunction "1_1") (pintype "passive"))
      (node (ref "J3") (pin "2") (pinfunction "2_2") (pintype "passive"))
      (node (ref "J3") (pin "3") (pinfunction "3_3") (pintype "passive"))
      (node (ref "J3") (pin "4") (pinfunction "4_4") (pintype "passive"))
      (node (ref "J3") (pin "5") (pinfunction "5_5") (pintype "passive"))
      (node (ref "J3") (pin "6") (pinfunction "6_6") (pintype "passive"))
      (node (ref "J4") (pin "7") (pinfunction "7_7") (pintype "passive"))
      (node (ref "J5") (pin "6") (pinfunction "6_6") (pintype "passive"))
      (node (ref "J5") (pin "7") (pinfunction "7_7") (pintype "passive"))
      (node (ref "J8") (pin "1") (pinfunction "1_1") (pintype "passive"))
      (node (ref "J8") (pin "2") (pinfunction "2_2") (pintype "passive"))
      (node (ref "J8") (pin "3") (pinfunction "3_3") (pintype "passive"))
      (node (ref "J8") (pin "4") (pinfunction "4_4") (pintype "passive"))
      (node (ref "J8") (pin "5") (pinfunction "5_5") (pintype "passive"))
      (node (ref "J8") (pin "6") (pinfunction "6_6") (pintype "passive"))
      (node (ref "J8") (pin "7") (pinfunction "7_7") (pintype "passive"))
      (node (ref "J8") (pin "8") (pinfunction "8_8") (pintype "passive"))
      (node (ref "LD0") (pin "K") (pinfunction "K_K") (pintype "passive"))
      (node (ref "LD1") (pin "K") (pinfunction "K_K") (pintype "passive"))
      (node (ref "LD2") (pin "K") (pinfunction "K_K") (pintype "passive"))
      (node (ref "LD3") (pin "K") (pinfunction "K_K") (pintype "passive"))
      (node (ref "LD4") (pin "K") (pinfunction "K_K") (pintype "passive"))
      (node (ref "LD5") (pin "K") (pinfunction "K_K") (pintype "passive"))
      (node (ref "LD6") (pin "K") (pinfunction "K_K") (pintype "passive"))
      (node (ref "LD7") (pin "K") (pinfunction "K_K") (pintype "passive"))
      (node (ref "R31") (pin "1") (pinfunction "1_1") (pintype "passive"))
      (node (ref "R32") (pin "1") (pinfunction "1_1") (pintype "passive"))
      (node (ref "U6") (pin "0") (pinfunction "TP_0") (pintype "power_in"))
      (node (ref "U6") (pin "9") (pinfunction "GND_&_TP_9") (pintype "power_in"))
      (node (ref "U7") (pin "0") (pinfunction "TP_0") (pintype "power_in"))
      (node (ref "U7") (pin "5") (pinfunction "A0_5") (pintype "input"))
      (node (ref "U7") (pin "6") (pinfunction "DGND_6") (pintype "power_in"))
      (node (ref "U7") (pin "8") (pinfunction "AGND_&_TP_8") (pintype "power_in"))
      (node (ref "U8") (pin "0") (pinfunction "TP_0") (pintype "power_in"))
      (node (ref "U8") (pin "11") (pinfunction "GND_&_TP_11") (pintype "power_in"))
      (node (ref "U9") (pin "0") (pinfunction "TP_0") (pintype "power_in"))
      (node (ref "U9") (pin "11") (pinfunction "GND_&_TP_11") (pintype "power_in"))
    )
    (net (code "73") (name "Net-(JP1-Pad2)") (class "Default")
      (node (ref "JP1") (pin "2") (pinfunction "2_2") (pintype "passive"))
      (node (ref "R19") (pin "1") (pinfunction "1_1") (pintype "passive"))
    )
    (net (code "74") (name "Net-(LD0-PadA)") (class "Default")
      (node (ref "LD0") (pin "A") (pinfunction "A_A") (pintype "passive"))
      (node (ref "R17") (pin "2") (pinfunction "2_2") (pintype "passive"))
    )
    (net (code "75") (name "Net-(LD1-PadA)") (class "Default")
      (node (ref "LD1") (pin "A") (pinfunction "A_A") (pintype "passive"))
      (node (ref "R18") (pin "2") (pinfunction "2_2") (pintype "passive"))
    )
    (net (code "76") (name "Net-(LD2-PadA)") (class "Default")
      (node (ref "LD2") (pin "A") (pinfunction "A_A") (pintype "passive"))
      (node (ref "R40") (pin "2") (pinfunction "2_2") (pintype "passive"))
    )
    (net (code "77") (name "Net-(LD3-PadA)") (class "Default")
      (node (ref "LD3") (pin "A") (pinfunction "A_A") (pintype "passive"))
      (node (ref "R41") (pin "2") (pinfunction "2_2") (pintype "passive"))
    )
    (net (code "78") (name "Net-(LD4-PadA)") (class "Default")
      (node (ref "LD4") (pin "A") (pinfunction "A_A") (pintype "passive"))
      (node (ref "R42") (pin "2") (pinfunction "2_2") (pintype "passive"))
    )
    (net (code "79") (name "Net-(LD5-PadA)") (class "Default")
      (node (ref "LD5") (pin "A") (pinfunction "A_A") (pintype "passive"))
      (node (ref "R43") (pin "2") (pinfunction "2_2") (pintype "passive"))
    )
    (net (code "80") (name "Net-(LD6-PadA)") (class "Default")
      (node (ref "LD6") (pin "A") (pinfunction "A_A") (pintype "passive"))
      (node (ref "R44") (pin "2") (pinfunction "2_2") (pintype "passive"))
    )
    (net (code "81") (name "Net-(LD7-PadA)") (class "Default")
      (node (ref "LD7") (pin "A") (pinfunction "A_A") (pintype "passive"))
      (node (ref "R45") (pin "2") (pinfunction "2_2") (pintype "passive"))
    )
    (net (code "82") (name "Net-(U7-ADCIN)") (class "Default")
      (node (ref "U7") (pin "13") (pinfunction "MUXOUT_13") (pintype "output"))
      (node (ref "U7") (pin "14") (pinfunction "ADCIN_14") (pintype "input"))
    )
    (net (code "83") (name "Net-(U7-AVDD)") (class "Default")
      (node (ref "C41") (pin "2") (pinfunction "2_2") (pintype "passive"))
      (node (ref "C46") (pin "1") (pinfunction "1_1") (pintype "passive"))
      (node (ref "R19") (pin "2") (pinfunction "2_2") (pintype "passive"))
      (node (ref "U7") (pin "15") (pinfunction "AVDD_15") (pintype "power_in"))
    )
    (net (code "84") (name "VIN") (class "Default")
      (node (ref "J5") (pin "8") (pinfunction "8_8") (pintype "passive"))
    )
    (net (code "85") (name "unconnected-(J5-Pad1)") (class "Default")
      (node (ref "J5") (pin "1") (pinfunction "1_1") (pintype "passive+no_connect"))
    )
    (net (code "86") (name "unconnected-(U7-PWRCON-Pad7)") (class "Default")
      (node (ref "U7") (pin "7") (pinfunction "PWRCON_7") (pintype "output+no_connect"))
    )
    (net (code "87") (name "unconnected-(U8-A1-Pad1)") (class "Default")
      (node (ref "U8") (pin "1") (pinfunction "A1_1") (pintype "bidirectional+no_connect"))
    )
    (net (code "88") (name "unconnected-(U8-A2-Pad3)") (class "Default")
      (node (ref "U8") (pin "3") (pinfunction "A2_3") (pintype "bidirectional+no_connect"))
    )
    (net (code "89") (name "unconnected-(U8-B1-Pad20)") (class "Default")
      (node (ref "U8") (pin "20") (pinfunction "B1_20") (pintype "bidirectional+no_connect"))
    )
    (net (code "90") (name "unconnected-(U8-B2-Pad18)") (class "Default")
      (node (ref "U8") (pin "18") (pinfunction "B2_18") (pintype "bidirectional+no_connect"))
    )
  )
)
